# LilyMini_Protosnap_updated.net
KiCad netlist of a schematic drawn in EAGLE
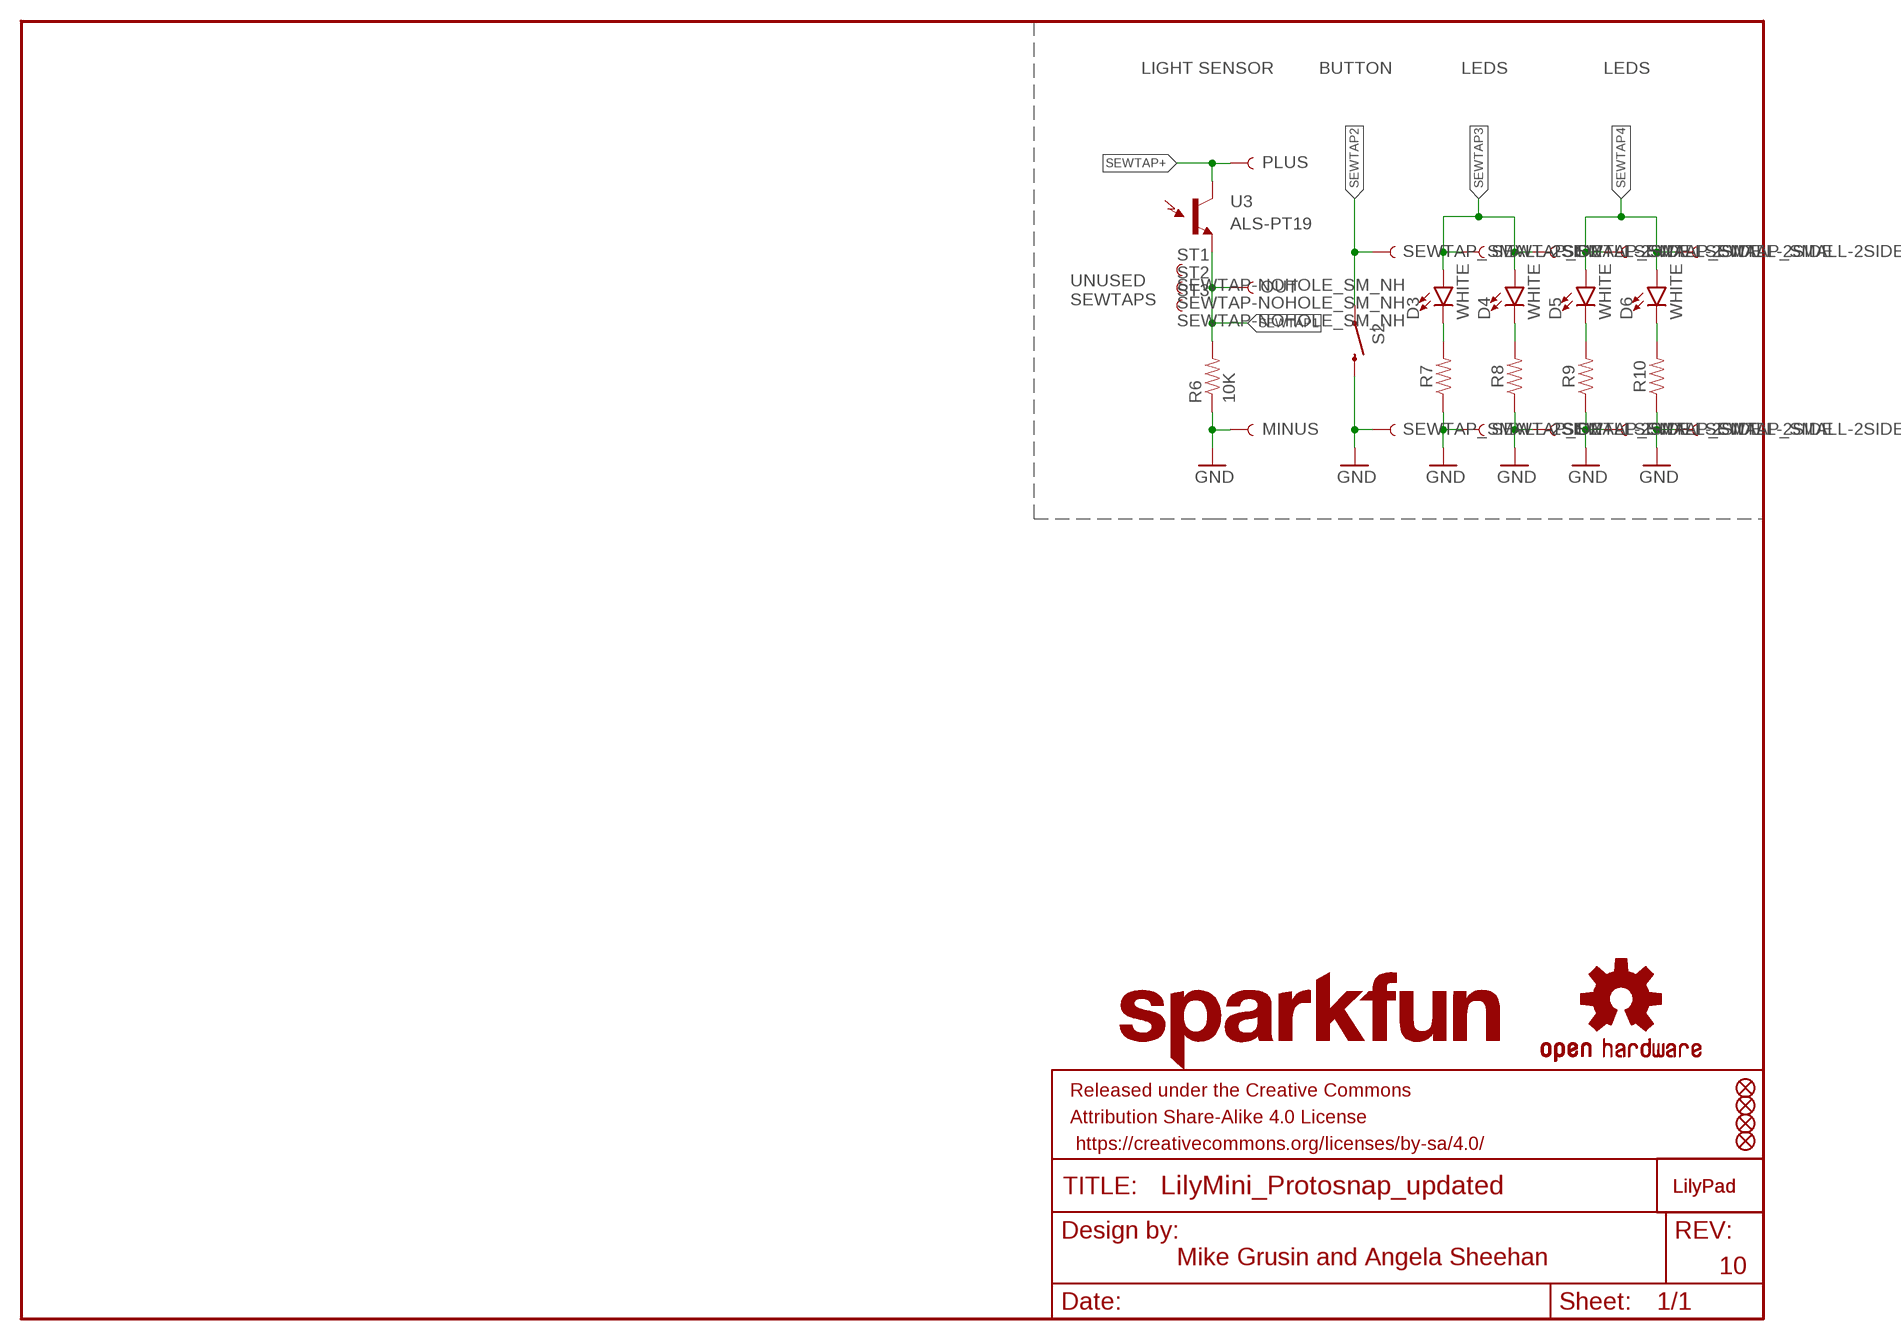
[diagram p0: schematic, sheet 1]

(export (version "E")
  (design (tool "Eeschema 10.0.6"))
  (components
    (comp (ref "$1_61_$_2016-09-25_21-56-09")
      (value "OSHW-LOGOS")
      (footprint "eagle-import:OSHW-LOGO-S")
      (libsource (lib "eagle-import") (part "OSHW-LOGOS"))
    )
    (comp (ref "D3")
      (value "WHITE")
      (footprint "eagle-import:LED-1206")
      (libsource (lib "eagle-import") (part "LED-WHITE1206"))
    )
    (comp (ref "D4")
      (value "WHITE")
      (footprint "eagle-import:LED-1206")
      (libsource (lib "eagle-import") (part "LED-WHITE1206"))
    )
    (comp (ref "D5")
      (value "WHITE")
      (footprint "eagle-import:LED-1206")
      (libsource (lib "eagle-import") (part "LED-WHITE1206"))
    )
    (comp (ref "D6")
      (value "WHITE")
      (footprint "eagle-import:LED-1206")
      (libsource (lib "eagle-import") (part "LED-WHITE1206"))
    )
    (comp (ref "FD1")
      (value "FIDUCIAL1X2")
      (footprint "eagle-import:FIDUCIAL-1X2")
      (libsource (lib "eagle-import") (part "FIDUCIAL1X2"))
    )
    (comp (ref "FD2")
      (value "FIDUCIAL1X2")
      (footprint "eagle-import:FIDUCIAL-1X2")
      (libsource (lib "eagle-import") (part "FIDUCIAL1X2"))
    )
    (comp (ref "FD3")
      (value "FIDUCIAL1X2")
      (footprint "eagle-import:FIDUCIAL-1X2")
      (libsource (lib "eagle-import") (part "FIDUCIAL1X2"))
    )
    (comp (ref "FD4")
      (value "FIDUCIAL1X2")
      (footprint "eagle-import:FIDUCIAL-1X2")
      (libsource (lib "eagle-import") (part "FIDUCIAL1X2"))
    )
    (comp (ref "FRAME1")
      (value "FRAME-LETTER")
      (footprint "eagle-import:CREATIVE_COMMONS")
      (libsource (lib "eagle-import") (part "FRAME-LETTER"))
    )
    (comp (ref "JP12")
      (value "SEWTAP_SMALL-2SIDE")
      (footprint "eagle-import:PETAL-SMALL-2SIDE")
      (libsource (lib "eagle-import") (part "SEWTAP_SMALL-2SIDE"))
    )
    (comp (ref "JP13")
      (value "SEWTAP_SMALL-2SIDE")
      (footprint "eagle-import:PETAL-SMALL-2SIDE")
      (libsource (lib "eagle-import") (part "SEWTAP_SMALL-2SIDE"))
    )
    (comp (ref "JP20")
      (value "SEWTAP_SMALL-2SIDE")
      (footprint "eagle-import:PETAL-SMALL-2SIDE")
      (libsource (lib "eagle-import") (part "SEWTAP_SMALL-2SIDE"))
    )
    (comp (ref "JP21")
      (value "SEWTAP_SMALL-2SIDE")
      (footprint "eagle-import:PETAL-SMALL-2SIDE")
      (libsource (lib "eagle-import") (part "SEWTAP_SMALL-2SIDE"))
    )
    (comp (ref "JP22")
      (value "SEWTAP_SMALL-2SIDE")
      (footprint "eagle-import:PETAL-SMALL-2SIDE")
      (libsource (lib "eagle-import") (part "SEWTAP_SMALL-2SIDE"))
    )
    (comp (ref "JP23")
      (value "SEWTAP_SMALL-2SIDE")
      (footprint "eagle-import:PETAL-SMALL-2SIDE")
      (libsource (lib "eagle-import") (part "SEWTAP_SMALL-2SIDE"))
    )
    (comp (ref "JP24")
      (value "SEWTAP_SMALL-2SIDE")
      (footprint "eagle-import:PETAL-SMALL-2SIDE")
      (libsource (lib "eagle-import") (part "SEWTAP_SMALL-2SIDE"))
    )
    (comp (ref "JP25")
      (value "SEWTAP_SMALL-2SIDE")
      (footprint "eagle-import:PETAL-SMALL-2SIDE")
      (libsource (lib "eagle-import") (part "SEWTAP_SMALL-2SIDE"))
    )
    (comp (ref "JP26")
      (value "SEWTAP_SMALL-2SIDE")
      (footprint "eagle-import:PETAL-SMALL-2SIDE")
      (libsource (lib "eagle-import") (part "SEWTAP_SMALL-2SIDE"))
    )
    (comp (ref "JP27")
      (value "SEWTAP_SMALL-2SIDE")
      (footprint "eagle-import:PETAL-SMALL-2SIDE")
      (libsource (lib "eagle-import") (part "SEWTAP_SMALL-2SIDE"))
    )
    (comp (ref "LOGO1")
      (value "LOGO-LPL")
      (footprint "eagle-import:LOGO-L")
      (libsource (lib "eagle-import") (part "LOGO-LPL"))
    )
    (comp (ref "LOGO2")
      (value "LILYLOGO-L-TOP")
      (footprint "eagle-import:LOGO-L-TOP")
      (libsource (lib "eagle-import") (part "LILYLOGO-L-TOP"))
    )
    (comp (ref "LOGO4")
      (value "SFE_LOGO_NAME.1_INCH")
      (footprint "eagle-import:SFE_LOGO_NAME_.1")
      (libsource (lib "eagle-import") (part "SFE_LOGO_NAME.1_INCH"))
    )
    (comp (ref "R6")
      (value "10K")
      (footprint "eagle-import:0603-RES")
      (libsource (lib "eagle-import") (part "10KOHM-1/10W-1%(0603)0603"))
    )
    (comp (ref "R7")
      (value "RESISTOR0603")
      (footprint "eagle-import:0603")
      (libsource (lib "eagle-import") (part "RESISTOR0603"))
    )
    (comp (ref "R8")
      (value "RESISTOR0603")
      (footprint "eagle-import:0603")
      (libsource (lib "eagle-import") (part "RESISTOR0603"))
    )
    (comp (ref "R9")
      (value "RESISTOR0603")
      (footprint "eagle-import:0603")
      (libsource (lib "eagle-import") (part "RESISTOR0603"))
    )
    (comp (ref "R10")
      (value "RESISTOR0603")
      (footprint "eagle-import:0603")
      (libsource (lib "eagle-import") (part "RESISTOR0603"))
    )
    (comp (ref "S2")
      (value "SWITCH-MOMENTARY-2SMD-REDUNDANT")
      (footprint "eagle-import:TACTILE-SWITCH-SMD")
      (libsource (lib "eagle-import") (part "SWITCH-MOMENTARY-2SMD-REDUNDANT"))
    )
    (comp (ref "SEWTAPLS+")
      (value "PLUS")
      (footprint "eagle-import:PETAL-SMALL-2SIDE")
      (libsource (lib "eagle-import") (part "SEWTAP_SMALL-2SIDE"))
    )
    (comp (ref "SEWTAPLS-")
      (value "MINUS")
      (footprint "eagle-import:PETAL-SMALL-2SIDE")
      (libsource (lib "eagle-import") (part "SEWTAP_SMALL-2SIDE"))
    )
    (comp (ref "SEWTAPLSOUT")
      (value "OUT")
      (footprint "eagle-import:PETAL-SMALL-2SIDE")
      (libsource (lib "eagle-import") (part "SEWTAP_SMALL-2SIDE"))
    )
    (comp (ref "ST1")
      (value "SEWTAP-NOHOLE_SM_NH")
      (footprint "eagle-import:PETAL-SMALL-NOHOLE")
      (libsource (lib "eagle-import") (part "SEWTAP-NOHOLE_SM_NH"))
    )
    (comp (ref "ST2")
      (value "SEWTAP-NOHOLE_SM_NH")
      (footprint "eagle-import:PETAL-SMALL-NOHOLE")
      (libsource (lib "eagle-import") (part "SEWTAP-NOHOLE_SM_NH"))
    )
    (comp (ref "ST3")
      (value "SEWTAP-NOHOLE_SM_NH")
      (footprint "eagle-import:PETAL-SMALL-NOHOLE")
      (libsource (lib "eagle-import") (part "SEWTAP-NOHOLE_SM_NH"))
    )
    (comp (ref "U3")
      (value "ALS-PT19")
      (footprint "eagle-import:ALS-PT19")
      (libsource (lib "eagle-import") (part "LIGHTSENSORALS"))
    )
  )
  (nets
    (net (code "1") (name "GND") (class "Default")
      (node (ref "JP13") (pin "1") (pinfunction "1_1") (pintype "bidirectional"))
      (node (ref "JP21") (pin "1") (pinfunction "1_1") (pintype "bidirectional"))
      (node (ref "JP23") (pin "1") (pinfunction "1_1") (pintype "bidirectional"))
      (node (ref "JP25") (pin "1") (pinfunction "1_1") (pintype "bidirectional"))
      (node (ref "JP27") (pin "1") (pinfunction "1_1") (pintype "bidirectional"))
      (node (ref "R10") (pin "1") (pinfunction "1_1") (pintype "passive"))
      (node (ref "R6") (pin "1") (pinfunction "1_1") (pintype "passive"))
      (node (ref "R7") (pin "1") (pinfunction "1_1") (pintype "passive"))
      (node (ref "R8") (pin "1") (pinfunction "1_1") (pintype "passive"))
      (node (ref "R9") (pin "1") (pinfunction "1_1") (pintype "passive"))
      (node (ref "S2") (pin "3") (pinfunction "2_3") (pintype "passive"))
      (node (ref "S2") (pin "4") (pinfunction "2_4") (pintype "passive"))
      (node (ref "SEWTAPLS-") (pin "1") (pinfunction "1_1") (pintype "bidirectional"))
    )
    (net (code "2") (name "Net-(D3-PadC)") (class "Default")
      (node (ref "D3") (pin "C") (pinfunction "C_C") (pintype "passive"))
      (node (ref "R7") (pin "2") (pinfunction "2_2") (pintype "passive"))
    )
    (net (code "3") (name "Net-(D4-PadC)") (class "Default")
      (node (ref "D4") (pin "C") (pinfunction "C_C") (pintype "passive"))
      (node (ref "R8") (pin "2") (pinfunction "2_2") (pintype "passive"))
    )
    (net (code "4") (name "Net-(D5-PadC)") (class "Default")
      (node (ref "D5") (pin "C") (pinfunction "C_C") (pintype "passive"))
      (node (ref "R9") (pin "2") (pinfunction "2_2") (pintype "passive"))
    )
    (net (code "5") (name "Net-(D6-PadC)") (class "Default")
      (node (ref "D6") (pin "C") (pinfunction "C_C") (pintype "passive"))
      (node (ref "R10") (pin "2") (pinfunction "2_2") (pintype "passive"))
    )
    (net (code "6") (name "SEWTAP+") (class "Default")
      (node (ref "SEWTAPLS+") (pin "1") (pinfunction "1_1") (pintype "bidirectional"))
      (node (ref "U3") (pin "C") (pinfunction "C1_C") (pintype "passive"))
    )
    (net (code "7") (name "SEWTAP1") (class "Default")
      (node (ref "R6") (pin "2") (pinfunction "2_2") (pintype "passive"))
      (node (ref "SEWTAPLSOUT") (pin "1") (pinfunction "1_1") (pintype "bidirectional"))
      (node (ref "U3") (pin "E") (pinfunction "E1_E") (pintype "passive"))
    )
    (net (code "8") (name "SEWTAP2") (class "Default")
      (node (ref "JP12") (pin "1") (pinfunction "1_1") (pintype "bidirectional"))
      (node (ref "S2") (pin "1") (pinfunction "1_1") (pintype "passive"))
      (node (ref "S2") (pin "2") (pinfunction "1_2") (pintype "passive"))
    )
    (net (code "9") (name "SEWTAP3") (class "Default")
      (node (ref "D3") (pin "A") (pinfunction "A_A") (pintype "passive"))
      (node (ref "D4") (pin "A") (pinfunction "A_A") (pintype "passive"))
      (node (ref "JP20") (pin "1") (pinfunction "1_1") (pintype "bidirectional"))
      (node (ref "JP22") (pin "1") (pinfunction "1_1") (pintype "bidirectional"))
    )
    (net (code "10") (name "SEWTAP4") (class "Default")
      (node (ref "D5") (pin "A") (pinfunction "A_A") (pintype "passive"))
      (node (ref "D6") (pin "A") (pinfunction "A_A") (pintype "passive"))
      (node (ref "JP24") (pin "1") (pinfunction "1_1") (pintype "bidirectional"))
      (node (ref "JP26") (pin "1") (pinfunction "1_1") (pintype "bidirectional"))
    )
  )
)
